# Schematic_Sensing_Module.net
KiCad netlist of a schematic drawn in EAGLE
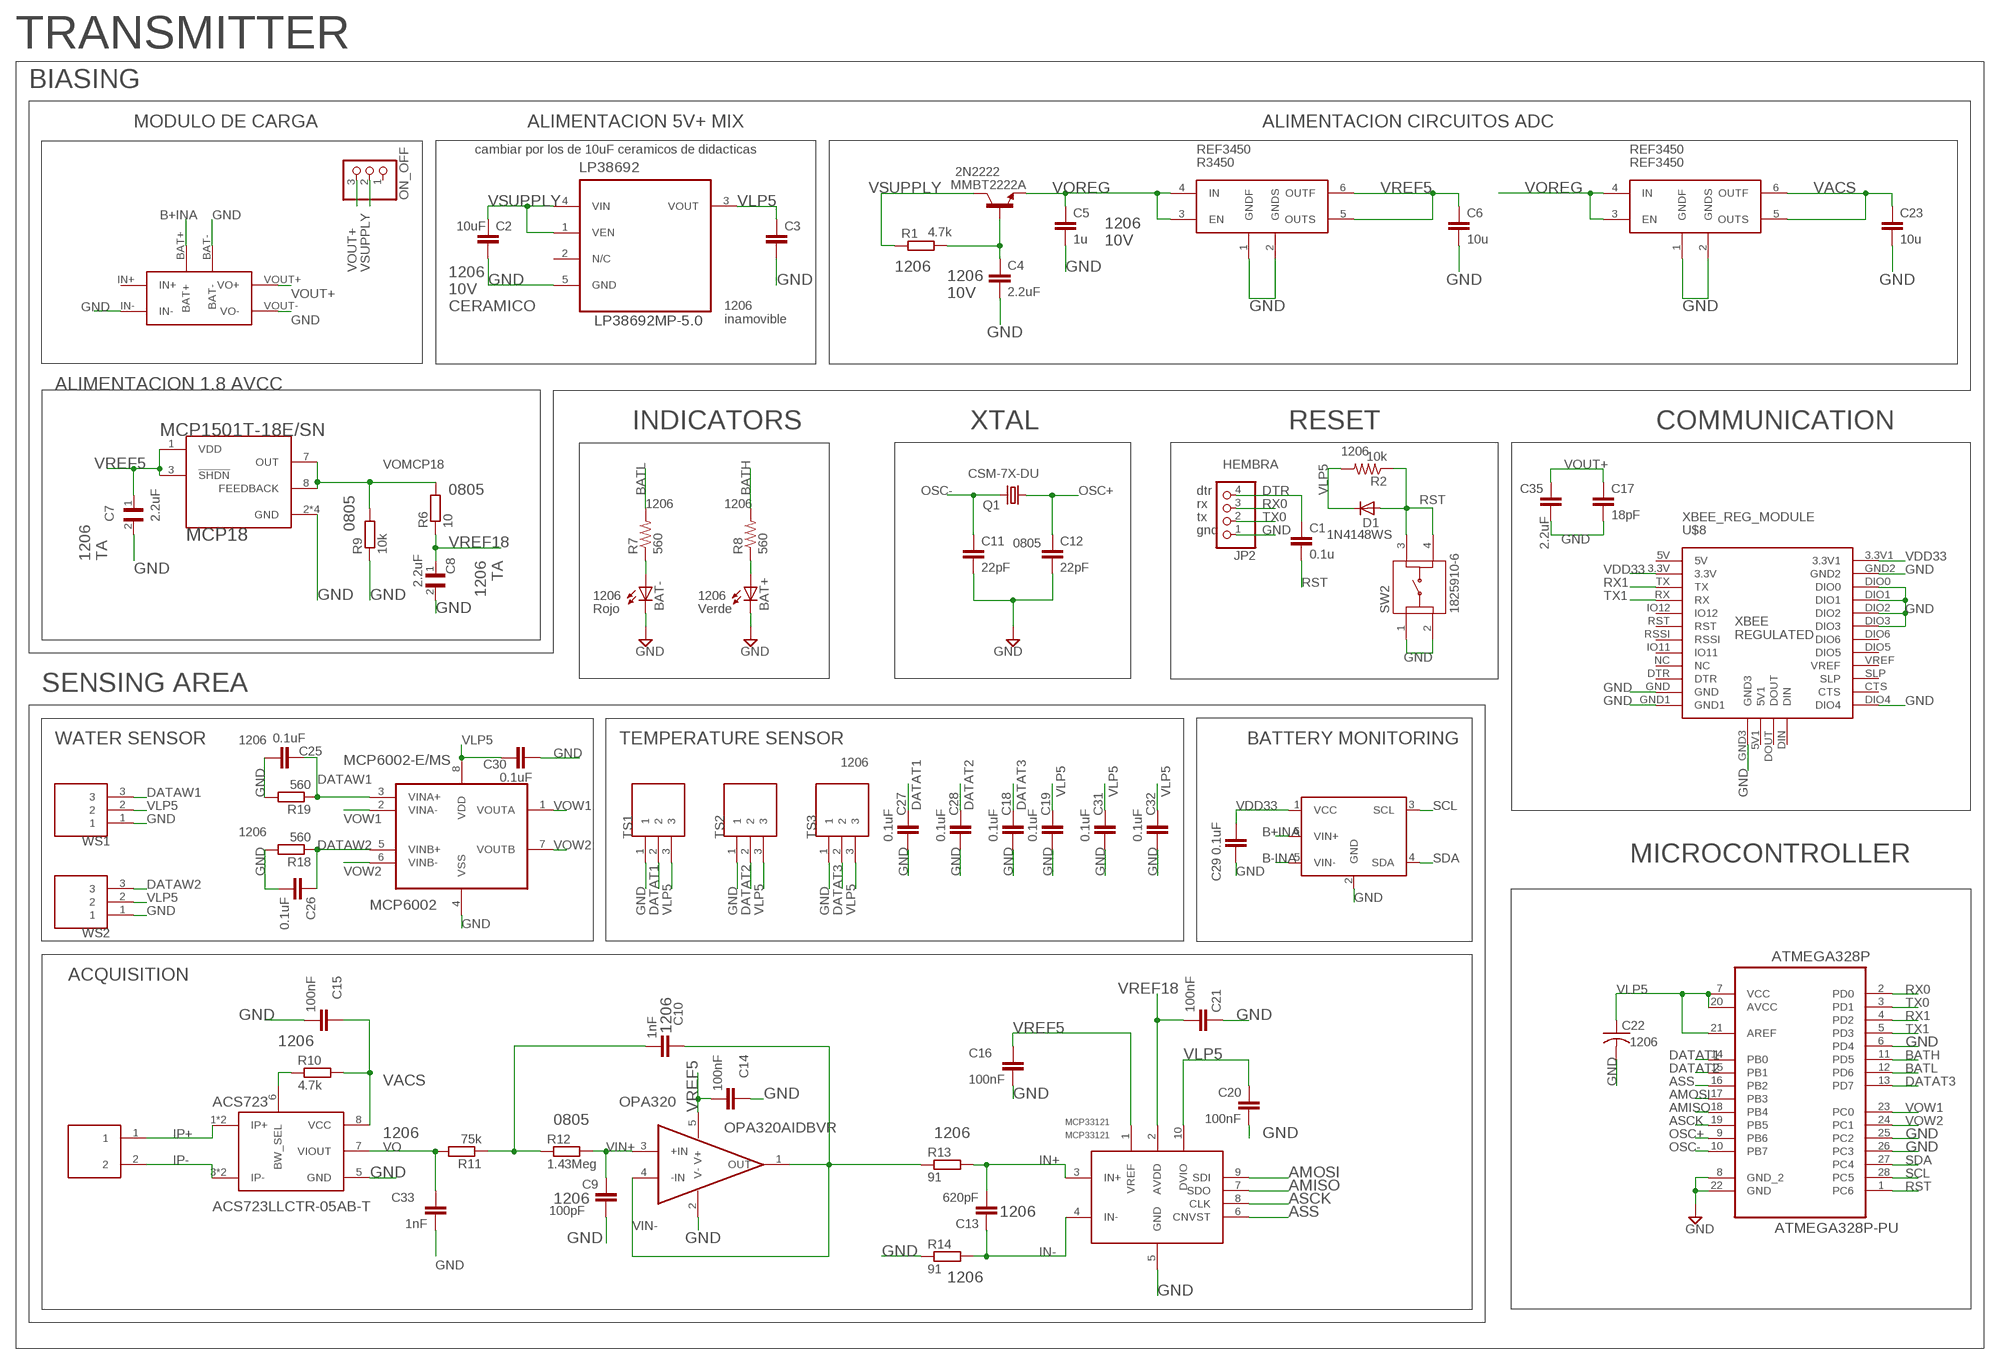
[diagram p0: schematic, sheet 1]

(export (version "E")
  (design (tool "Eeschema 10.0.6"))
  (components
    (comp (ref "2N2222")
      (value "MMBT2222A")
      (footprint "eagle-import:SOT23")
      (fields (field (name "MF") "ON Semiconductor"))
      (libsource (lib "eagle-import") (part "MMBT2222A"))
    )
    (comp (ref "ACS723")
      (value "ACS723LLCTR-05AB-T")
      (footprint "eagle-import:SOIC127P600X175-8N")
      (fields (field (name "MF") "ALPS"))
      (libsource (lib "eagle-import") (part "ACS723LLCTR-05AB-T"))
    )
    (comp (ref "ATMEGA328P")
      (value "ATMEGA328P-PU")
      (footprint "eagle-import:DIP254P762X457-28")
      (libsource (lib "eagle-import") (part "ATMEGA328P-PU"))
    )
    (comp (ref "BAT+")
      (value "LEDCHIPLED_1206")
      (footprint "eagle-import:CHIPLED_1206")
      (libsource (lib "eagle-import") (part "LEDCHIPLED_1206"))
    )
    (comp (ref "BAT-")
      (value "LEDCHIPLED_1206")
      (footprint "eagle-import:CHIPLED_1206")
      (libsource (lib "eagle-import") (part "LEDCHIPLED_1206"))
    )
    (comp (ref "C1")
      (value "0.1u")
      (footprint "eagle-import:C0805")
      (libsource (lib "eagle-import") (part "C-EUC0805"))
    )
    (comp (ref "C2")
      (value "10uF")
      (footprint "eagle-import:C1206")
      (libsource (lib "eagle-import") (part "rcl_334_C-EUC1206"))
    )
    (comp (ref "C3")
      (value "10uF")
      (footprint "eagle-import:C1206")
      (libsource (lib "eagle-import") (part "rcl_334_C-EUC1206"))
    )
    (comp (ref "C4")
      (value "2.2uF")
      (footprint "eagle-import:C1206")
      (libsource (lib "eagle-import") (part "rcl_334_C-EUC1206"))
    )
    (comp (ref "C5")
      (value "1u")
      (footprint "eagle-import:C1206")
      (libsource (lib "eagle-import") (part "rcl_334_C-EUC1206"))
    )
    (comp (ref "C6")
      (value "10u")
      (footprint "eagle-import:C1206")
      (libsource (lib "eagle-import") (part "rcl_334_C-EUC1206"))
    )
    (comp (ref "C7")
      (value "2.2uF")
      (footprint "eagle-import:CAPC3216X110N")
      (fields
        (field (name "DIGI-KEY_PART_NUMBER") "399-8268-2-ND")
        (field (name "MF") "KEMET")
        (field (name "MP") "T491A106K010AT7280")
      )
      (libsource (lib "eagle-import") (part "T491A106K010AT7280"))
    )
    (comp (ref "C8")
      (value "2.2uF")
      (footprint "eagle-import:CAPC3216X110N")
      (fields
        (field (name "DIGI-KEY_PART_NUMBER") "399-8268-2-ND")
        (field (name "MF") "KEMET")
        (field (name "MP") "T491A106K010AT7280")
      )
      (libsource (lib "eagle-import") (part "T491A106K010AT7280"))
    )
    (comp (ref "C9")
      (value "100pF")
      (footprint "eagle-import:C1206")
      (libsource (lib "eagle-import") (part "rcl_334_C-EUC1206"))
    )
    (comp (ref "C10")
      (value "1nF")
      (footprint "eagle-import:C1206")
      (libsource (lib "eagle-import") (part "rcl_334_C-EUC1206"))
    )
    (comp (ref "C11")
      (value "22pF")
      (footprint "eagle-import:C0805")
      (libsource (lib "eagle-import") (part "rcl_334_C-EUC0805"))
    )
    (comp (ref "C12")
      (value "22pF")
      (footprint "eagle-import:C0805")
      (libsource (lib "eagle-import") (part "rcl_334_C-EUC0805"))
    )
    (comp (ref "C13")
      (value "620pF")
      (footprint "eagle-import:C1206")
      (libsource (lib "eagle-import") (part "rcl_334_C-EUC1206"))
    )
    (comp (ref "C14")
      (value "100nF")
      (footprint "eagle-import:C1206")
      (libsource (lib "eagle-import") (part "rcl_334_C-EUC1206"))
    )
    (comp (ref "C15")
      (value "100nF")
      (footprint "eagle-import:C1206")
      (libsource (lib "eagle-import") (part "rcl_334_C-EUC1206"))
    )
    (comp (ref "C16")
      (value "100nF")
      (footprint "eagle-import:C1206")
      (libsource (lib "eagle-import") (part "rcl_334_C-EUC1206"))
    )
    (comp (ref "C17")
      (value "18pF")
      (footprint "eagle-import:C0805")
      (libsource (lib "eagle-import") (part "C-EUC0805"))
    )
    (comp (ref "C18")
      (value "0.1uF")
      (footprint "eagle-import:C1206")
      (libsource (lib "eagle-import") (part "rcl_334_C-EUC1206"))
    )
    (comp (ref "C19")
      (value "0.1uF")
      (footprint "eagle-import:C1206")
      (libsource (lib "eagle-import") (part "rcl_334_C-EUC1206"))
    )
    (comp (ref "C20")
      (value "100nF")
      (footprint "eagle-import:C1206")
      (libsource (lib "eagle-import") (part "rcl_334_C-EUC1206"))
    )
    (comp (ref "C21")
      (value "100nF")
      (footprint "eagle-import:C1206")
      (libsource (lib "eagle-import") (part "rcl_334_C-EUC1206"))
    )
    (comp (ref "C22")
      (value "0.1uF")
      (footprint "eagle-import:C1206")
      (libsource (lib "eagle-import") (part "C-USC1206"))
    )
    (comp (ref "C23")
      (value "10u")
      (footprint "eagle-import:C1206")
      (libsource (lib "eagle-import") (part "rcl_334_C-EUC1206"))
    )
    (comp (ref "C25")
      (value "0.1uF")
      (footprint "eagle-import:C1206")
      (libsource (lib "eagle-import") (part "rcl_334_C-EUC1206"))
    )
    (comp (ref "C26")
      (value "0.1uF")
      (footprint "eagle-import:C1206")
      (libsource (lib "eagle-import") (part "rcl_334_C-EUC1206"))
    )
    (comp (ref "C27")
      (value "0.1uF")
      (footprint "eagle-import:C1206")
      (libsource (lib "eagle-import") (part "rcl_334_C-EUC1206"))
    )
    (comp (ref "C28")
      (value "0.1uF")
      (footprint "eagle-import:C1206")
      (libsource (lib "eagle-import") (part "rcl_334_C-EUC1206"))
    )
    (comp (ref "C29")
      (value "0.1uF")
      (footprint "eagle-import:C1206")
      (libsource (lib "eagle-import") (part "rcl_334_C-EUC1206"))
    )
    (comp (ref "C30")
      (value "0.1uF")
      (footprint "eagle-import:C1206")
      (libsource (lib "eagle-import") (part "rcl_334_C-EUC1206"))
    )
    (comp (ref "C31")
      (value "0.1uF")
      (footprint "eagle-import:C1206")
      (libsource (lib "eagle-import") (part "rcl_334_C-EUC1206"))
    )
    (comp (ref "C32")
      (value "0.1uF")
      (footprint "eagle-import:C1206")
      (libsource (lib "eagle-import") (part "rcl_334_C-EUC1206"))
    )
    (comp (ref "C33")
      (value "1nF")
      (footprint "eagle-import:C1206")
      (libsource (lib "eagle-import") (part "rcl_334_C-EUC1206"))
    )
    (comp (ref "C35")
      (value "2.2uF")
      (footprint "eagle-import:C1206")
      (libsource (lib "eagle-import") (part "rcl_334_C-EUC1206"))
    )
    (comp (ref "D1")
      (value "1N4148WS")
      (footprint "eagle-import:SOD323")
      (fields (field (name "MF") "ON Semiconductor"))
      (libsource (lib "eagle-import") (part "1N4148WS"))
    )
    (comp (ref "IACT")
      (value "TERMINAL-TB2")
      (footprint "eagle-import:TERMINAL-TB2")
      (libsource (lib "eagle-import") (part "TERMINAL-TB2"))
    )
    (comp (ref "INA219")
      (value "INABB")
      (footprint "eagle-import:INA219-MODULE")
      (libsource (lib "eagle-import") (part "INABB"))
    )
    (comp (ref "JP2")
      (value "PINHD-1X4")
      (footprint "eagle-import:1X04")
      (libsource (lib "eagle-import") (part "PINHD-1X4"))
    )
    (comp (ref "LP38692")
      (value "LP38692MP-5.0")
      (footprint "eagle-import:SOT150P696X180-5N")
      (fields (field (name "MF") "Texas Instruments"))
      (libsource (lib "eagle-import") (part "LP38692MP-5.0"))
    )
    (comp (ref "MCP18")
      (value "MCP1501T-18E/SN")
      (footprint "eagle-import:SOIC127P600X175-8N")
      (fields (field (name "MF") "Microchip"))
      (libsource (lib "eagle-import") (part "MCP1501T-18E/SN"))
    )
    (comp (ref "MCP6002")
      (value "MCP6002-E/MS")
      (footprint "eagle-import:SOP65P490X110-8N")
      (fields (field (name "MF") "Microchip Technology"))
      (libsource (lib "eagle-import") (part "MCP6002-E/MS"))
    )
    (comp (ref "MCP33121")
      (value "MCP33121")
      (footprint "eagle-import:MSOP10")
      (libsource (lib "eagle-import") (part "MCP33121"))
    )
    (comp (ref "ON_OFF")
      (value "PINHD-1X3")
      (footprint "eagle-import:1X03")
      (libsource (lib "eagle-import") (part "PINHD-1X3"))
    )
    (comp (ref "OPA320")
      (value "OPA320AIDBVR")
      (footprint "eagle-import:SOT95P280X145-5N")
      (fields (field (name "DIGI-KEY_PART_NUMBER") "296-29480-1-ND") (field (name "MF") "Texas Instruments"))
      (libsource (lib "eagle-import") (part "OPA320AIDBVR"))
    )
    (comp (ref "Q1")
      (value "CSM-7X-DU")
      (footprint "eagle-import:CSM-7X-DU")
      (libsource (lib "eagle-import") (part "CSM-7X-DU"))
    )
    (comp (ref "R1")
      (value "4.7k")
      (footprint "eagle-import:R1206")
      (libsource (lib "eagle-import") (part "R-EU_R1206"))
    )
    (comp (ref "R2")
      (value "10k")
      (footprint "eagle-import:R1206")
      (libsource (lib "eagle-import") (part "R-US_R1206"))
    )
    (comp (ref "R6")
      (value "10")
      (footprint "eagle-import:R0805")
      (libsource (lib "eagle-import") (part "R-EU_R0805"))
    )
    (comp (ref "R7")
      (value "560")
      (footprint "eagle-import:R1206")
      (libsource (lib "eagle-import") (part "R-US_R1206"))
    )
    (comp (ref "R8")
      (value "560")
      (footprint "eagle-import:R1206")
      (libsource (lib "eagle-import") (part "R-US_R1206"))
    )
    (comp (ref "R9")
      (value "10k")
      (footprint "eagle-import:R0805")
      (libsource (lib "eagle-import") (part "R-EU_R0805"))
    )
    (comp (ref "R10")
      (value "4.7k")
      (footprint "eagle-import:M1206")
      (libsource (lib "eagle-import") (part "R-EU_M1206"))
    )
    (comp (ref "R11")
      (value "75k")
      (footprint "eagle-import:R1206")
      (libsource (lib "eagle-import") (part "R-EU_R1206"))
    )
    (comp (ref "R12")
      (value "1.43Meg")
      (footprint "eagle-import:R0805")
      (libsource (lib "eagle-import") (part "R-EU_R0805"))
    )
    (comp (ref "R13")
      (value "91")
      (footprint "eagle-import:R1206")
      (libsource (lib "eagle-import") (part "R-EU_R1206"))
    )
    (comp (ref "R14")
      (value "91")
      (footprint "eagle-import:R1206")
      (libsource (lib "eagle-import") (part "R-EU_R1206"))
    )
    (comp (ref "R18")
      (value "560")
      (footprint "eagle-import:R1206")
      (libsource (lib "eagle-import") (part "R-EU_R1206"))
    )
    (comp (ref "R19")
      (value "560")
      (footprint "eagle-import:R1206")
      (libsource (lib "eagle-import") (part "R-EU_R1206"))
    )
    (comp (ref "R3450")
      (value "REF3450")
      (footprint "eagle-import:SOT95P280X145-6N")
      (libsource (lib "eagle-import") (part "REF3450"))
    )
    (comp (ref "REF3450")
      (value "REF3450")
      (footprint "eagle-import:SOT95P280X145-6N")
      (libsource (lib "eagle-import") (part "REF3450"))
    )
    (comp (ref "SW2")
      (value "1825910-6")
      (footprint "eagle-import:SW_1825910-6-4")
      (fields (field (name "MF") "TE Connectivity"))
      (libsource (lib "eagle-import") (part "1825910-6"))
    )
    (comp (ref "TS1")
      (value "TERMINAL-TB3")
      (footprint "eagle-import:TERMINAL-TB3")
      (fields (field (name "MF") "CUI Devices") (field (name "MP") "TB001-500-03BE"))
      (libsource (lib "eagle-import") (part "TERMINAL-TB3"))
    )
    (comp (ref "TS2")
      (value "TERMINAL-TB3")
      (footprint "eagle-import:TERMINAL-TB3")
      (fields (field (name "MF") "CUI Devices") (field (name "MP") "TB001-500-03BE"))
      (libsource (lib "eagle-import") (part "TERMINAL-TB3"))
    )
    (comp (ref "TS3")
      (value "TERMINAL-TB3")
      (footprint "eagle-import:TERMINAL-TB3")
      (fields (field (name "MF") "CUI Devices") (field (name "MP") "TB001-500-03BE"))
      (libsource (lib "eagle-import") (part "TERMINAL-TB3"))
    )
    (comp (ref "U$1")
      (value "MODULO_CARGA_DEVICE")
      (footprint "eagle-import:MODULO_CARGA")
      (libsource (lib "eagle-import") (part "MODULO_CARGA_DEVICE"))
    )
    (comp (ref "U$8")
      (value "XBEE_REG_MODULE")
      (footprint "eagle-import:XBEE_REG")
      (libsource (lib "eagle-import") (part "XBEE_REG_MODULE"))
    )
    (comp (ref "WS1")
      (value "TERMINAL-TB3")
      (footprint "eagle-import:TERMINAL-TB3")
      (fields (field (name "MF") "CUI Devices") (field (name "MP") "TB001-500-03BE"))
      (libsource (lib "eagle-import") (part "TERMINAL-TB3"))
    )
    (comp (ref "WS2")
      (value "TERMINAL-TB3")
      (footprint "eagle-import:TERMINAL-TB3")
      (fields (field (name "MF") "CUI Devices") (field (name "MP") "TB001-500-03BE"))
      (libsource (lib "eagle-import") (part "TERMINAL-TB3"))
    )
  )
  (nets
    (net (code "1") (name "/AMISO") (class "Default")
      (node (ref "ATMEGA328P") (pin "18") (pinfunction "PB4_18") (pintype "bidirectional"))
      (node (ref "MCP33121") (pin "7") (pinfunction "SDO_7") (pintype "bidirectional"))
    )
    (net (code "2") (name "/AMOSI") (class "Default")
      (node (ref "ATMEGA328P") (pin "17") (pinfunction "PB3_17") (pintype "bidirectional"))
      (node (ref "MCP33121") (pin "9") (pinfunction "SDI_9") (pintype "bidirectional"))
    )
    (net (code "3") (name "/ASCK") (class "Default")
      (node (ref "ATMEGA328P") (pin "19") (pinfunction "PB5_19") (pintype "bidirectional"))
      (node (ref "MCP33121") (pin "8") (pinfunction "CLK_8") (pintype "bidirectional"))
    )
    (net (code "4") (name "/ASS") (class "Default")
      (node (ref "ATMEGA328P") (pin "16") (pinfunction "PB2_16") (pintype "bidirectional"))
      (node (ref "MCP33121") (pin "6") (pinfunction "CNVST_6") (pintype "bidirectional"))
    )
    (net (code "5") (name "/B+INA") (class "Default")
      (node (ref "INA219") (pin "6") (pinfunction "VIN+_6") (pintype "bidirectional"))
      (node (ref "U$1") (pin "BAT+") (pinfunction "BAT+_BAT+") (pintype "bidirectional"))
    )
    (net (code "6") (name "/B-INA") (class "Default")
      (node (ref "INA219") (pin "5") (pinfunction "VIN-_5") (pintype "bidirectional"))
    )
    (net (code "7") (name "/BATH") (class "Default")
      (node (ref "ATMEGA328P") (pin "11") (pinfunction "PD5_11") (pintype "bidirectional"))
      (node (ref "R8") (pin "2") (pinfunction "2_2") (pintype "passive"))
    )
    (net (code "8") (name "/BATL") (class "Default")
      (node (ref "ATMEGA328P") (pin "12") (pinfunction "PD6_12") (pintype "bidirectional"))
      (node (ref "R7") (pin "2") (pinfunction "2_2") (pintype "passive"))
    )
    (net (code "9") (name "/DATAT1") (class "Default")
      (node (ref "ATMEGA328P") (pin "14") (pinfunction "PB0_14") (pintype "bidirectional"))
      (node (ref "C27") (pin "1") (pinfunction "1_1") (pintype "passive"))
      (node (ref "TS1") (pin "2") (pinfunction "2_2") (pintype "passive"))
    )
    (net (code "10") (name "/DATAT2") (class "Default")
      (node (ref "ATMEGA328P") (pin "15") (pinfunction "PB1_15") (pintype "bidirectional"))
      (node (ref "C28") (pin "1") (pinfunction "1_1") (pintype "passive"))
      (node (ref "TS2") (pin "2") (pinfunction "2_2") (pintype "passive"))
    )
    (net (code "11") (name "/DATAT3") (class "Default")
      (node (ref "ATMEGA328P") (pin "13") (pinfunction "PD7_13") (pintype "bidirectional"))
      (node (ref "C18") (pin "1") (pinfunction "1_1") (pintype "passive"))
      (node (ref "TS3") (pin "2") (pinfunction "2_2") (pintype "passive"))
    )
    (net (code "12") (name "/DATAW1") (class "Default")
      (node (ref "C25") (pin "1") (pinfunction "1_1") (pintype "passive"))
      (node (ref "MCP6002") (pin "3") (pinfunction "VINA+_3") (pintype "input"))
      (node (ref "R19") (pin "1") (pinfunction "1_1") (pintype "passive"))
      (node (ref "WS1") (pin "3") (pinfunction "3_3") (pintype "passive"))
    )
    (net (code "13") (name "/DATAW2") (class "Default")
      (node (ref "C26") (pin "1") (pinfunction "1_1") (pintype "passive"))
      (node (ref "MCP6002") (pin "5") (pinfunction "VINB+_5") (pintype "input"))
      (node (ref "R18") (pin "1") (pinfunction "1_1") (pintype "passive"))
      (node (ref "WS2") (pin "3") (pinfunction "3_3") (pintype "passive"))
    )
    (net (code "14") (name "/DTR") (class "Default")
      (node (ref "C1") (pin "1") (pinfunction "1_1") (pintype "passive"))
      (node (ref "JP2") (pin "4") (pinfunction "4_4") (pintype "passive"))
    )
    (net (code "15") (name "/IN+") (class "Default")
      (node (ref "C13") (pin "2") (pinfunction "2_2") (pintype "passive"))
      (node (ref "MCP33121") (pin "3") (pinfunction "IN+_3") (pintype "bidirectional"))
      (node (ref "R13") (pin "2") (pinfunction "2_2") (pintype "passive"))
    )
    (net (code "16") (name "/IN-") (class "Default")
      (node (ref "C13") (pin "1") (pinfunction "1_1") (pintype "passive"))
      (node (ref "MCP33121") (pin "4") (pinfunction "IN-_4") (pintype "bidirectional"))
      (node (ref "R14") (pin "2") (pinfunction "2_2") (pintype "passive"))
    )
    (net (code "17") (name "/IP+") (class "Default")
      (node (ref "ACS723") (pin "1") (pinfunction "IP+_1") (pintype "passive"))
      (node (ref "ACS723") (pin "2") (pinfunction "IP+_2") (pintype "passive"))
      (node (ref "IACT") (pin "1") (pinfunction "1_1") (pintype "bidirectional"))
    )
    (net (code "18") (name "/IP-") (class "Default")
      (node (ref "ACS723") (pin "3") (pinfunction "IP-_3") (pintype "passive"))
      (node (ref "ACS723") (pin "4") (pinfunction "IP-_4") (pintype "passive"))
      (node (ref "IACT") (pin "2") (pinfunction "2_2") (pintype "bidirectional"))
    )
    (net (code "19") (name "/OSC+") (class "Default")
      (node (ref "ATMEGA328P") (pin "9") (pinfunction "PB6_9") (pintype "bidirectional"))
      (node (ref "C12") (pin "1") (pinfunction "1_1") (pintype "passive"))
      (node (ref "Q1") (pin "1") (pinfunction "1_1") (pintype "passive"))
    )
    (net (code "20") (name "/OSC-") (class "Default")
      (node (ref "ATMEGA328P") (pin "10") (pinfunction "PB7_10") (pintype "bidirectional"))
      (node (ref "C11") (pin "1") (pinfunction "1_1") (pintype "passive"))
      (node (ref "Q1") (pin "2") (pinfunction "2_2") (pintype "passive"))
    )
    (net (code "21") (name "/RST") (class "Default")
      (node (ref "ATMEGA328P") (pin "1") (pinfunction "PC6_1") (pintype "bidirectional"))
      (node (ref "C1") (pin "2") (pinfunction "2_2") (pintype "passive"))
      (node (ref "D1") (pin "A") (pinfunction "A_A") (pintype "passive"))
      (node (ref "R2") (pin "1") (pinfunction "1_1") (pintype "passive"))
      (node (ref "SW2") (pin "3") (pinfunction "3_3") (pintype "passive"))
      (node (ref "SW2") (pin "4") (pinfunction "4_4") (pintype "passive"))
    )
    (net (code "22") (name "/RX0") (class "Default")
      (node (ref "ATMEGA328P") (pin "2") (pinfunction "PD0_2") (pintype "bidirectional"))
      (node (ref "JP2") (pin "3") (pinfunction "3_3") (pintype "passive"))
    )
    (net (code "23") (name "/RX1") (class "Default")
      (node (ref "ATMEGA328P") (pin "4") (pinfunction "PD2_4") (pintype "bidirectional"))
      (node (ref "U$8") (pin "TX") (pinfunction "TX_TX") (pintype "bidirectional"))
    )
    (net (code "24") (name "/SCL") (class "Default")
      (node (ref "ATMEGA328P") (pin "28") (pinfunction "PC5_28") (pintype "bidirectional"))
      (node (ref "INA219") (pin "3") (pinfunction "SCL_3") (pintype "bidirectional"))
    )
    (net (code "25") (name "/SDA") (class "Default")
      (node (ref "ATMEGA328P") (pin "27") (pinfunction "PC4_27") (pintype "bidirectional"))
      (node (ref "INA219") (pin "4") (pinfunction "SDA_4") (pintype "bidirectional"))
    )
    (net (code "26") (name "/TX0") (class "Default")
      (node (ref "ATMEGA328P") (pin "3") (pinfunction "PD1_3") (pintype "bidirectional"))
      (node (ref "JP2") (pin "2") (pinfunction "2_2") (pintype "passive"))
    )
    (net (code "27") (name "/TX1") (class "Default")
      (node (ref "ATMEGA328P") (pin "5") (pinfunction "PD3_5") (pintype "bidirectional"))
      (node (ref "U$8") (pin "RX") (pinfunction "RX_RX") (pintype "bidirectional"))
    )
    (net (code "28") (name "/VACS") (class "Default")
      (node (ref "ACS723") (pin "8") (pinfunction "VCC_8") (pintype "power_in"))
      (node (ref "C15") (pin "1") (pinfunction "1_1") (pintype "passive"))
      (node (ref "C23") (pin "1") (pinfunction "1_1") (pintype "passive"))
      (node (ref "R10") (pin "2") (pinfunction "2_2") (pintype "passive"))
      (node (ref "REF3450") (pin "5") (pinfunction "OUTS_5") (pintype "bidirectional"))
      (node (ref "REF3450") (pin "6") (pinfunction "OUTF_6") (pintype "bidirectional"))
    )
    (net (code "29") (name "/VDD33") (class "Default")
      (node (ref "C29") (pin "1") (pinfunction "1_1") (pintype "passive"))
      (node (ref "INA219") (pin "1") (pinfunction "VCC_1") (pintype "bidirectional"))
      (node (ref "U$8") (pin "3.3V") (pinfunction "3.3V_3.3V") (pintype "bidirectional"))
      (node (ref "U$8") (pin "3.3V1") (pinfunction "3.3V1_3.3V1") (pintype "bidirectional"))
    )
    (net (code "30") (name "/VIN+") (class "Default")
      (node (ref "C9") (pin "1") (pinfunction "1_1") (pintype "passive"))
      (node (ref "OPA320") (pin "3") (pinfunction "+IN_3") (pintype "input"))
      (node (ref "R12") (pin "2") (pinfunction "2_2") (pintype "passive"))
    )
    (net (code "31") (name "/VIN-") (class "Default")
      (node (ref "C10") (pin "1") (pinfunction "1_1") (pintype "passive"))
      (node (ref "OPA320") (pin "1") (pinfunction "OUT_1") (pintype "output"))
      (node (ref "OPA320") (pin "4") (pinfunction "-IN_4") (pintype "input"))
      (node (ref "R13") (pin "1") (pinfunction "1_1") (pintype "passive"))
    )
    (net (code "32") (name "/VLP5") (class "Default")
      (node (ref "ATMEGA328P") (pin "20") (pinfunction "AVCC_20") (pintype "power_in"))
      (node (ref "ATMEGA328P") (pin "21") (pinfunction "AREF_21") (pintype "input"))
      (node (ref "ATMEGA328P") (pin "7") (pinfunction "VCC_7") (pintype "power_in"))
      (node (ref "C19") (pin "1") (pinfunction "1_1") (pintype "passive"))
      (node (ref "C20") (pin "1") (pinfunction "1_1") (pintype "passive"))
      (node (ref "C22") (pin "1") (pinfunction "1_1") (pintype "passive"))
      (node (ref "C3") (pin "1") (pinfunction "1_1") (pintype "passive"))
      (node (ref "C30") (pin "1") (pinfunction "1_1") (pintype "passive"))
      (node (ref "C31") (pin "1") (pinfunction "1_1") (pintype "passive"))
      (node (ref "C32") (pin "1") (pinfunction "1_1") (pintype "passive"))
      (node (ref "D1") (pin "C") (pinfunction "C_C") (pintype "passive"))
      (node (ref "LP38692") (pin "3") (pinfunction "VOUT_3") (pintype "output"))
      (node (ref "MCP33121") (pin "10") (pinfunction "DVIO_10") (pintype "bidirectional"))
      (node (ref "MCP6002") (pin "8") (pinfunction "VDD_8") (pintype "power_in"))
      (node (ref "R2") (pin "2") (pinfunction "2_2") (pintype "passive"))
      (node (ref "TS1") (pin "3") (pinfunction "3_3") (pintype "passive"))
      (node (ref "TS2") (pin "3") (pinfunction "3_3") (pintype "passive"))
      (node (ref "TS3") (pin "3") (pinfunction "3_3") (pintype "passive"))
      (node (ref "WS1") (pin "2") (pinfunction "2_2") (pintype "passive"))
      (node (ref "WS2") (pin "2") (pinfunction "2_2") (pintype "passive"))
    )
    (net (code "33") (name "/VO") (class "Default")
      (node (ref "ACS723") (pin "7") (pinfunction "VIOUT_7") (pintype "output"))
      (node (ref "C33") (pin "1") (pinfunction "1_1") (pintype "passive"))
      (node (ref "R11") (pin "2") (pinfunction "2_2") (pintype "passive"))
    )
    (net (code "34") (name "/VOMCP18") (class "Default")
      (node (ref "MCP18") (pin "7") (pinfunction "OUT_7") (pintype "output"))
      (node (ref "MCP18") (pin "8") (pinfunction "FEEDBACK_8") (pintype "passive"))
      (node (ref "R6") (pin "2") (pinfunction "2_2") (pintype "passive"))
      (node (ref "R9") (pin "2") (pinfunction "2_2") (pintype "passive"))
    )
    (net (code "35") (name "/VOREG") (class "Default")
      (node (ref "2N2222") (pin "2") (pinfunction "E_2") (pintype "passive"))
      (node (ref "C5") (pin "1") (pinfunction "1_1") (pintype "passive"))
      (node (ref "R3450") (pin "3") (pinfunction "EN_3") (pintype "bidirectional"))
      (node (ref "R3450") (pin "4") (pinfunction "IN_4") (pintype "bidirectional"))
      (node (ref "REF3450") (pin "3") (pinfunction "EN_3") (pintype "bidirectional"))
      (node (ref "REF3450") (pin "4") (pinfunction "IN_4") (pintype "bidirectional"))
    )
    (net (code "36") (name "/VOUT+") (class "Default")
      (node (ref "C17") (pin "1") (pinfunction "1_1") (pintype "passive"))
      (node (ref "C35") (pin "1") (pinfunction "1_1") (pintype "passive"))
      (node (ref "ON_OFF") (pin "3") (pinfunction "3_3") (pintype "passive"))
      (node (ref "U$1") (pin "VOUT+") (pinfunction "VO+_VOUT+") (pintype "bidirectional"))
    )
    (net (code "37") (name "/VOW1") (class "Default")
      (node (ref "ATMEGA328P") (pin "23") (pinfunction "PC0_23") (pintype "bidirectional"))
      (node (ref "MCP6002") (pin "1") (pinfunction "VOUTA_1") (pintype "output"))
      (node (ref "MCP6002") (pin "2") (pinfunction "VINA-_2") (pintype "input"))
    )
    (net (code "38") (name "/VOW2") (class "Default")
      (node (ref "ATMEGA328P") (pin "24") (pinfunction "PC1_24") (pintype "bidirectional"))
      (node (ref "MCP6002") (pin "6") (pinfunction "VINB-_6") (pintype "input"))
      (node (ref "MCP6002") (pin "7") (pinfunction "VOUTB_7") (pintype "output"))
    )
    (net (code "39") (name "/VREF5") (class "Default")
      (node (ref "C14") (pin "2") (pinfunction "2_2") (pintype "passive"))
      (node (ref "C16") (pin "1") (pinfunction "1_1") (pintype "passive"))
      (node (ref "C6") (pin "1") (pinfunction "1_1") (pintype "passive"))
      (node (ref "C7") (pin "1") (pinfunction "1_1") (pintype "passive"))
      (node (ref "MCP18") (pin "1") (pinfunction "VDD_1") (pintype "power_in"))
      (node (ref "MCP18") (pin "3") (pinfunction "~{SHDN}_3") (pintype "input"))
      (node (ref "MCP33121") (pin "1") (pinfunction "VREF_1") (pintype "bidirectional"))
      (node (ref "OPA320") (pin "5") (pinfunction "V+_5") (pintype "power_in"))
      (node (ref "R3450") (pin "5") (pinfunction "OUTS_5") (pintype "bidirectional"))
      (node (ref "R3450") (pin "6") (pinfunction "OUTF_6") (pintype "bidirectional"))
    )
    (net (code "40") (name "/VREF18") (class "Default")
      (node (ref "C21") (pin "2") (pinfunction "2_2") (pintype "passive"))
      (node (ref "C8") (pin "1") (pinfunction "1_1") (pintype "passive"))
      (node (ref "MCP33121") (pin "2") (pinfunction "AVDD_2") (pintype "bidirectional"))
      (node (ref "R6") (pin "1") (pinfunction "1_1") (pintype "passive"))
    )
    (net (code "41") (name "/VSUPPLY") (class "Default")
      (node (ref "2N2222") (pin "3") (pinfunction "C_3") (pintype "passive"))
      (node (ref "C2") (pin "1") (pinfunction "1_1") (pintype "passive"))
      (node (ref "LP38692") (pin "1") (pinfunction "VEN_1") (pintype "input"))
      (node (ref "LP38692") (pin "4") (pinfunction "VIN_4") (pintype "power_in"))
      (node (ref "ON_OFF") (pin "2") (pinfunction "2_2") (pintype "passive"))
      (node (ref "R1") (pin "1") (pinfunction "1_1") (pintype "passive"))
    )
    (net (code "42") (name "GND") (class "Default")
      (node (ref "ACS723") (pin "5") (pinfunction "GND_5") (pintype "power_in"))
      (node (ref "ATMEGA328P") (pin "22") (pinfunction "GND_22") (pintype "passive"))
      (node (ref "ATMEGA328P") (pin "25") (pinfunction "PC2_25") (pintype "bidirectional"))
      (node (ref "ATMEGA328P") (pin "26") (pinfunction "PC3_26") (pintype "bidirectional"))
      (node (ref "ATMEGA328P") (pin "6") (pinfunction "PD4_6") (pintype "bidirectional"))
      (node (ref "ATMEGA328P") (pin "8") (pinfunction "GND_2_8") (pintype "passive"))
      (node (ref "BAT+") (pin "C") (pinfunction "C_C") (pintype "passive"))
      (node (ref "BAT-") (pin "C") (pinfunction "C_C") (pintype "passive"))
      (node (ref "C11") (pin "2") (pinfunction "2_2") (pintype "passive"))
      (node (ref "C12") (pin "2") (pinfunction "2_2") (pintype "passive"))
      (node (ref "C14") (pin "1") (pinfunction "1_1") (pintype "passive"))
      (node (ref "C15") (pin "2") (pinfunction "2_2") (pintype "passive"))
      (node (ref "C16") (pin "2") (pinfunction "2_2") (pintype "passive"))
      (node (ref "C17") (pin "2") (pinfunction "2_2") (pintype "passive"))
      (node (ref "C18") (pin "2") (pinfunction "2_2") (pintype "passive"))
      (node (ref "C19") (pin "2") (pinfunction "2_2") (pintype "passive"))
      (node (ref "C2") (pin "2") (pinfunction "2_2") (pintype "passive"))
      (node (ref "C20") (pin "2") (pinfunction "2_2") (pintype "passive"))
      (node (ref "C21") (pin "1") (pinfunction "1_1") (pintype "passive"))
      (node (ref "C22") (pin "2") (pinfunction "2_2") (pintype "passive"))
      (node (ref "C23") (pin "2") (pinfunction "2_2") (pintype "passive"))
      (node (ref "C25") (pin "2") (pinfunction "2_2") (pintype "passive"))
      (node (ref "C26") (pin "2") (pinfunction "2_2") (pintype "passive"))
      (node (ref "C27") (pin "2") (pinfunction "2_2") (pintype "passive"))
      (node (ref "C28") (pin "2") (pinfunction "2_2") (pintype "passive"))
      (node (ref "C29") (pin "2") (pinfunction "2_2") (pintype "passive"))
      (node (ref "C3") (pin "2") (pinfunction "2_2") (pintype "passive"))
      (node (ref "C30") (pin "2") (pinfunction "2_2") (pintype "passive"))
      (node (ref "C31") (pin "2") (pinfunction "2_2") (pintype "passive"))
      (node (ref "C32") (pin "2") (pinfunction "2_2") (pintype "passive"))
      (node (ref "C33") (pin "2") (pinfunction "2_2") (pintype "passive"))
      (node (ref "C35") (pin "2") (pinfunction "2_2") (pintype "passive"))
      (node (ref "C4") (pin "2") (pinfunction "2_2") (pintype "passive"))
      (node (ref "C5") (pin "2") (pinfunction "2_2") (pintype "passive"))
      (node (ref "C6") (pin "2") (pinfunction "2_2") (pintype "passive"))
      (node (ref "C7") (pin "2") (pinfunction "2_2") (pintype "passive"))
      (node (ref "C8") (pin "2") (pinfunction "2_2") (pintype "passive"))
      (node (ref "C9") (pin "2") (pinfunction "2_2") (pintype "passive"))
      (node (ref "INA219") (pin "2") (pinfunction "GND_2") (pintype "bidirectional"))
      (node (ref "JP2") (pin "1") (pinfunction "1_1") (pintype "passive"))
      (node (ref "LP38692") (pin "5") (pinfunction "GND_5") (pintype "passive"))
      (node (ref "MCP18") (pin "2") (pinfunction "GND_2") (pintype "passive"))
      (node (ref "MCP18") (pin "4") (pinfunction "GND_4") (pintype "passive"))
      (node (ref "MCP18") (pin "5") (pinfunction "GND_5") (pintype "passive"))
      (node (ref "MCP18") (pin "6") (pinfunction "GND_6") (pintype "passive"))
      (node (ref "MCP33121") (pin "5") (pinfunction "GND_5") (pintype "bidirectional"))
      (node (ref "MCP6002") (pin "4") (pinfunction "VSS_4") (pintype "power_in"))
      (node (ref "OPA320") (pin "2") (pinfunction "V-_2") (pintype "power_in"))
      (node (ref "R14") (pin "1") (pinfunction "1_1") (pintype "passive"))
      (node (ref "R18") (pin "2") (pinfunction "2_2") (pintype "passive"))
      (node (ref "R19") (pin "2") (pinfunction "2_2") (pintype "passive"))
      (node (ref "R3450") (pin "1") (pinfunction "GNDF_1") (pintype "bidirectional"))
      (node (ref "R3450") (pin "2") (pinfunction "GNDS_2") (pintype "bidirectional"))
      (node (ref "R9") (pin "1") (pinfunction "1_1") (pintype "passive"))
      (node (ref "REF3450") (pin "1") (pinfunction "GNDF_1") (pintype "bidirectional"))
      (node (ref "REF3450") (pin "2") (pinfunction "GNDS_2") (pintype "bidirectional"))
      (node (ref "SW2") (pin "1") (pinfunction "1_1") (pintype "passive"))
      (node (ref "SW2") (pin "2") (pinfunction "2_2") (pintype "passive"))
      (node (ref "TS1") (pin "1") (pinfunction "1_1") (pintype "passive"))
      (node (ref "TS2") (pin "1") (pinfunction "1_1") (pintype "passive"))
      (node (ref "TS3") (pin "1") (pinfunction "1_1") (pintype "passive"))
      (node (ref "U$1") (pin "BAT-") (pinfunction "BAT-_BAT-") (pintype "bidirectional"))
      (node (ref "U$1") (pin "IN-") (pinfunction "IN-_IN-") (pintype "bidirectional"))
      (node (ref "U$1") (pin "VOUT-") (pinfunction "VO-_VOUT-") (pintype "bidirectional"))
      (node (ref "U$8") (pin "DIO0") (pinfunction "DIO0_DIO0") (pintype "bidirectional"))
      (node (ref "U$8") (pin "DIO1") (pinfunction "DIO1_DIO1") (pintype "bidirectional"))
      (node (ref "U$8") (pin "DIO2") (pinfunction "DIO2_DIO2") (pintype "bidirectional"))
      (node (ref "U$8") (pin "DIO3") (pinfunction "DIO3_DIO3") (pintype "bidirectional"))
      (node (ref "U$8") (pin "DIO4") (pinfunction "DIO4_DIO4") (pintype "bidirectional"))
      (node (ref "U$8") (pin "GND") (pinfunction "GND_GND") (pintype "bidirectional"))
      (node (ref "U$8") (pin "GND1") (pinfunction "GND1_GND1") (pintype "bidirectional"))
      (node (ref "U$8") (pin "GND2") (pinfunction "GND2_GND2") (pintype "bidirectional"))
      (node (ref "U$8") (pin "GND3") (pinfunction "GND3_GND3") (pintype "bidirectional"))
      (node (ref "WS1") (pin "1") (pinfunction "1_1") (pintype "passive"))
      (node (ref "WS2") (pin "1") (pinfunction "1_1") (pintype "passive"))
    )
    (net (code "43") (name "Net-(2N2222-B)") (class "Default")
      (node (ref "2N2222") (pin "1") (pinfunction "B_1") (pintype "passive"))
      (node (ref "C4") (pin "1") (pinfunction "1_1") (pintype "passive"))
      (node (ref "R1") (pin "2") (pinfunction "2_2") (pintype "passive"))
    )
    (net (code "44") (name "Net-(ACS723-BW_SEL)") (class "Default")
      (node (ref "ACS723") (pin "6") (pinfunction "BW_SEL_6") (pintype "input"))
      (node (ref "R10") (pin "1") (pinfunction "1_1") (pintype "passive"))
    )
    (net (code "45") (name "Net-(BAT+-PadA)") (class "Default")
      (node (ref "BAT+") (pin "A") (pinfunction "A_A") (pintype "passive"))
      (node (ref "R8") (pin "1") (pinfunction "1_1") (pintype "passive"))
    )
    (net (code "46") (name "Net-(BAT--PadA)") (class "Default")
      (node (ref "BAT-") (pin "A") (pinfunction "A_A") (pintype "passive"))
      (node (ref "R7") (pin "1") (pinfunction "1_1") (pintype "passive"))
    )
    (net (code "47") (name "Net-(C10-Pad2)") (class "Default")
      (node (ref "C10") (pin "2") (pinfunction "2_2") (pintype "passive"))
      (node (ref "R11") (pin "1") (pinfunction "1_1") (pintype "passive"))
      (node (ref "R12") (pin "1") (pinfunction "1_1") (pintype "passive"))
    )
    (net (code "48") (name "unconnected-(LP38692-N{slash}C-Pad2)") (class "Default")
      (node (ref "LP38692") (pin "2") (pinfunction "N/C_2") (pintype "no_connect"))
    )
    (net (code "49") (name "unconnected-(ON_OFF-Pad1)") (class "Default")
      (node (ref "ON_OFF") (pin "1") (pinfunction "1_1") (pintype "passive"))
    )
    (net (code "50") (name "unconnected-(U$1-PadIN+)") (class "Default")
      (node (ref "U$1") (pin "IN+") (pinfunction "IN+_IN+") (pintype "bidirectional"))
    )
    (net (code "51") (name "unconnected-(U$8-Pad5V)") (class "Default")
      (node (ref "U$8") (pin "5V") (pinfunction "5V_5V") (pintype "bidirectional"))
    )
    (net (code "52") (name "unconnected-(U$8-Pad5V1)") (class "Default")
      (node (ref "U$8") (pin "5V1") (pinfunction "5V1_5V1") (pintype "bidirectional"))
    )
    (net (code "53") (name "unconnected-(U$8-PadCTS)") (class "Default")
      (node (ref "U$8") (pin "CTS") (pinfunction "CTS_CTS") (pintype "bidirectional"))
    )
    (net (code "54") (name "unconnected-(U$8-PadDIN)") (class "Default")
      (node (ref "U$8") (pin "DIN") (pinfunction "DIN_DIN") (pintype "bidirectional"))
    )
    (net (code "55") (name "unconnected-(U$8-PadDIO5)") (class "Default")
      (node (ref "U$8") (pin "DIO5") (pinfunction "DIO5_DIO5") (pintype "bidirectional"))
    )
    (net (code "56") (name "unconnected-(U$8-PadDIO6)") (class "Default")
      (node (ref "U$8") (pin "DIO6") (pinfunction "DIO6_DIO6") (pintype "bidirectional"))
    )
    (net (code "57") (name "unconnected-(U$8-PadDOUT)") (class "Default")
      (node (ref "U$8") (pin "DOUT") (pinfunction "DOUT_DOUT") (pintype "bidirectional"))
    )
    (net (code "58") (name "unconnected-(U$8-PadDTR)") (class "Default")
      (node (ref "U$8") (pin "DTR") (pinfunction "DTR_DTR") (pintype "bidirectional"))
    )
    (net (code "59") (name "unconnected-(U$8-PadIO11)") (class "Default")
      (node (ref "U$8") (pin "IO11") (pinfunction "IO11_IO11") (pintype "bidirectional"))
    )
    (net (code "60") (name "unconnected-(U$8-PadIO12)") (class "Default")
      (node (ref "U$8") (pin "IO12") (pinfunction "IO12_IO12") (pintype "bidirectional"))
    )
    (net (code "61") (name "unconnected-(U$8-PadNC)") (class "Default")
      (node (ref "U$8") (pin "NC") (pinfunction "NC_NC") (pintype "bidirectional"))
    )
    (net (code "62") (name "unconnected-(U$8-PadRSSI)") (class "Default")
      (node (ref "U$8") (pin "RSSI") (pinfunction "RSSI_RSSI") (pintype "bidirectional"))
    )
    (net (code "63") (name "unconnected-(U$8-PadRST)") (class "Default")
      (node (ref "U$8") (pin "RST") (pinfunction "RST_RST") (pintype "bidirectional"))
    )
    (net (code "64") (name "unconnected-(U$8-PadSLP)") (class "Default")
      (node (ref "U$8") (pin "SLP") (pinfunction "SLP_SLP") (pintype "bidirectional"))
    )
    (net (code "65") (name "unconnected-(U$8-PadVREF)") (class "Default")
      (node (ref "U$8") (pin "VREF") (pinfunction "VREF_VREF") (pintype "bidirectional"))
    )
  )
)
